# Keyboard_SYS.net
KiCad netlist of a schematic drawn in Altium Designer
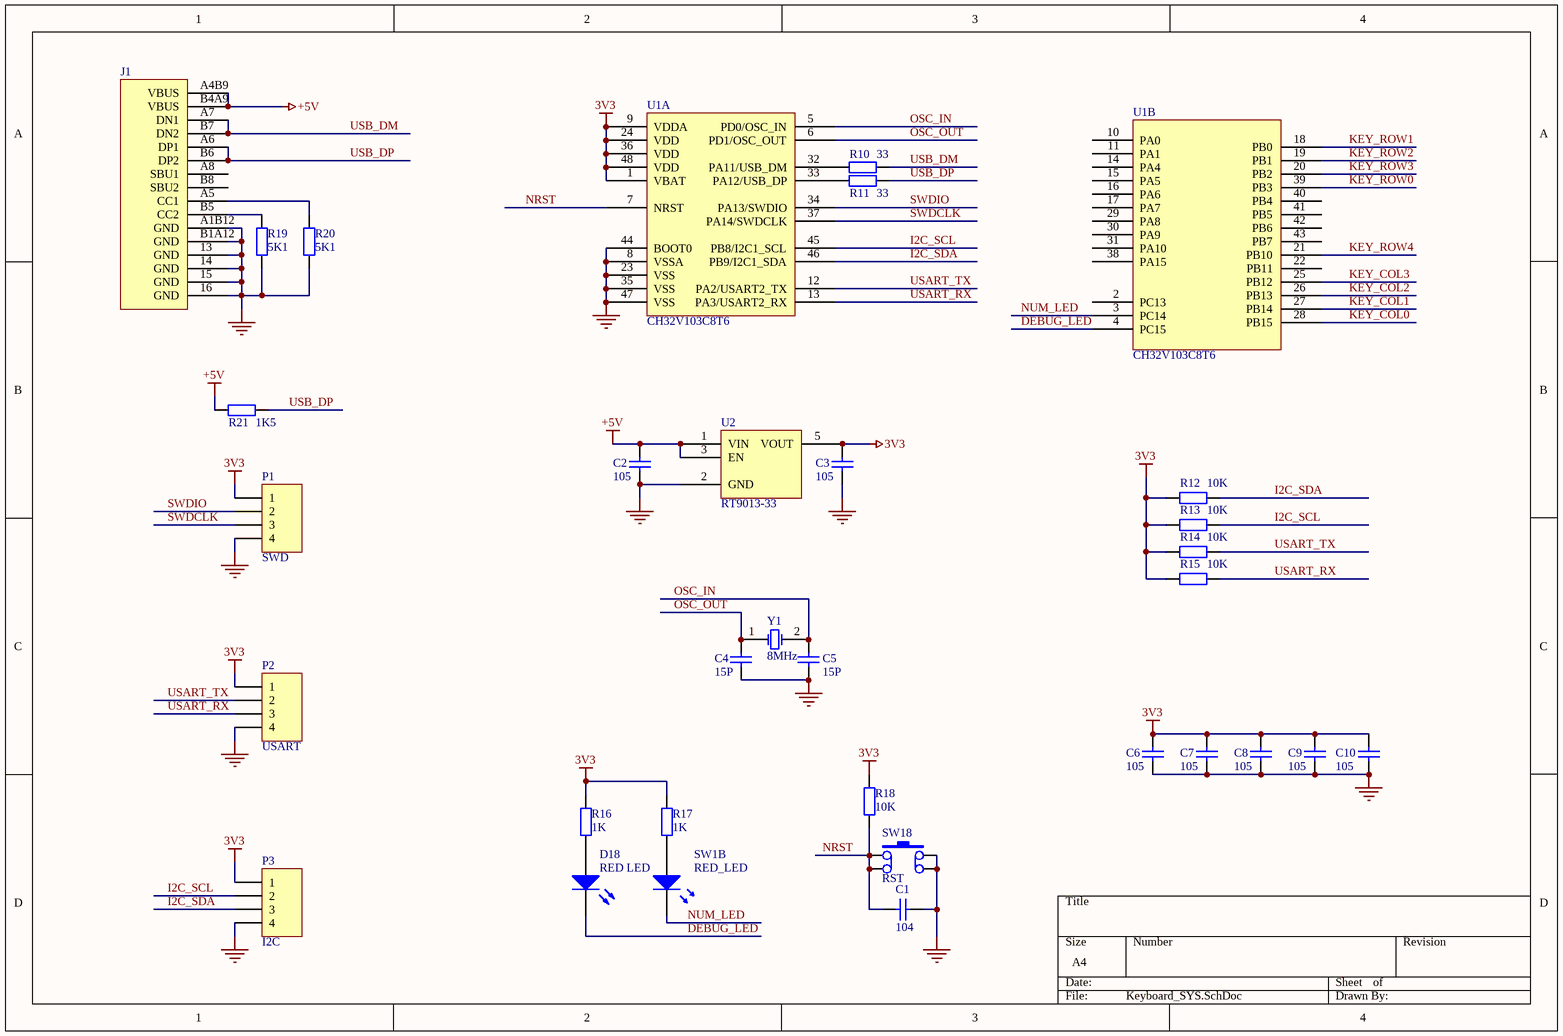
[diagram p0: Keyboard_SYS.SchDoc]

(export (version "E")
  (design (tool "Eeschema 10.0.6"))
  (components
    (comp (ref "C1")
      (value "104")
      (footprint "Devices:C0603")
      (description "Capacitor (Semiconductor SIM Model)")
      (fields (field (name "PUBLISHER") "Altium Limited"))
      (libsource (lib "Miscellaneous Devices") (part "Cap Semi"))
    )
    (comp (ref "C2")
      (value "105")
      (footprint "Devices:C0603")
      (description "Capacitor (Semiconductor SIM Model)")
      (fields (field (name "PUBLISHER") "Altium Limited"))
      (libsource (lib "Miscellaneous Devices") (part "Cap Semi"))
    )
    (comp (ref "C3")
      (value "105")
      (footprint "Devices:C0603")
      (description "Capacitor (Semiconductor SIM Model)")
      (fields (field (name "PUBLISHER") "Altium Limited"))
      (libsource (lib "Miscellaneous Devices") (part "Cap Semi"))
    )
    (comp (ref "C4")
      (value "15P")
      (footprint "Devices:C0603")
      (description "Capacitor (Semiconductor SIM Model)")
      (fields (field (name "PUBLISHER") "Altium Limited"))
      (libsource (lib "Miscellaneous Devices") (part "Cap Semi"))
    )
    (comp (ref "C5")
      (value "15P")
      (footprint "Devices:C0603")
      (description "Capacitor (Semiconductor SIM Model)")
      (fields (field (name "PUBLISHER") "Altium Limited"))
      (libsource (lib "Miscellaneous Devices") (part "Cap Semi"))
    )
    (comp (ref "C6")
      (value "105")
      (footprint "Devices:C0603")
      (description "Capacitor (Semiconductor SIM Model)")
      (fields (field (name "PUBLISHER") "Altium Limited"))
      (libsource (lib "Miscellaneous Devices") (part "Cap Semi"))
    )
    (comp (ref "C7")
      (value "105")
      (footprint "Devices:C0603")
      (description "Capacitor (Semiconductor SIM Model)")
      (fields (field (name "PUBLISHER") "Altium Limited"))
      (libsource (lib "Miscellaneous Devices") (part "Cap Semi"))
    )
    (comp (ref "C8")
      (value "105")
      (footprint "Devices:C0603")
      (description "Capacitor (Semiconductor SIM Model)")
      (fields (field (name "PUBLISHER") "Altium Limited"))
      (libsource (lib "Miscellaneous Devices") (part "Cap Semi"))
    )
    (comp (ref "C9")
      (value "105")
      (footprint "Devices:C0603")
      (description "Capacitor (Semiconductor SIM Model)")
      (fields (field (name "PUBLISHER") "Altium Limited"))
      (libsource (lib "Miscellaneous Devices") (part "Cap Semi"))
    )
    (comp (ref "C10")
      (value "105")
      (footprint "Devices:C0603")
      (description "Capacitor (Semiconductor SIM Model)")
      (fields (field (name "PUBLISHER") "Altium Limited"))
      (libsource (lib "Miscellaneous Devices") (part "Cap Semi"))
    )
    (comp (ref "D18")
      (value "RED LED")
      (footprint "Devices:LED0603-RED")
      (description "Typical RED, GREEN, YELLOW, AMBER GaAs LED")
      (fields (field (name "PUBLISHER") "Altium Limited"))
      (libsource (lib "Miscellaneous Devices") (part "LED2"))
    )
    (comp (ref "J1")
      (value "TYPEC-304S-ACP16")
      (footprint "Devices:USB-C-SMD_TYPEC-304-BCP16")
      (libsource (lib "Devices") (part "TYPEC-304S-ACP16"))
    )
    (comp (ref "P1")
      (value "SWD")
      (footprint "Devices:SIP4")
      (description "Header, 4-Pin")
      (fields (field (name "PUBLISHER") "Altium Limited"))
      (libsource (lib "Miscellaneous Connectors") (part "Header 4"))
    )
    (comp (ref "P2")
      (value "USART")
      (footprint "Devices:SIP4")
      (description "Header, 4-Pin")
      (fields (field (name "PUBLISHER") "Altium Limited"))
      (libsource (lib "Miscellaneous Connectors") (part "Header 4"))
    )
    (comp (ref "P3")
      (value "I2C")
      (footprint "Devices:SIP4")
      (description "Header, 4-Pin")
      (fields (field (name "PUBLISHER") "Altium Limited"))
      (libsource (lib "Miscellaneous Connectors") (part "Header 4"))
    )
    (comp (ref "R10")
      (value "33")
      (footprint "Devices:R0603")
      (description "Resistor")
      (fields (field (name "PUBLISHER") "Altium Limited"))
      (libsource (lib "Miscellaneous Devices") (part "Res2"))
    )
    (comp (ref "R11")
      (value "33")
      (footprint "Devices:R0603")
      (description "Resistor")
      (fields (field (name "PUBLISHER") "Altium Limited"))
      (libsource (lib "Miscellaneous Devices") (part "Res2"))
    )
    (comp (ref "R12")
      (value "10K")
      (footprint "Devices:R0603")
      (description "Resistor")
      (fields (field (name "PUBLISHER") "Altium Limited"))
      (libsource (lib "") (part "Res2_3"))
    )
    (comp (ref "R13")
      (value "10K")
      (footprint "Devices:R0603")
      (description "Resistor")
      (fields (field (name "PUBLISHER") "Altium Limited"))
      (libsource (lib "") (part "Res2_3"))
    )
    (comp (ref "R14")
      (value "10K")
      (footprint "Devices:R0603")
      (description "Resistor")
      (fields (field (name "PUBLISHER") "Altium Limited"))
      (libsource (lib "") (part "Res2_3"))
    )
    (comp (ref "R15")
      (value "10K")
      (footprint "Devices:R0603")
      (description "Resistor")
      (fields (field (name "PUBLISHER") "Altium Limited"))
      (libsource (lib "") (part "Res2_3"))
    )
    (comp (ref "R16")
      (value "1K")
      (footprint "Devices:R0603")
      (description "Resistor")
      (fields (field (name "PUBLISHER") "Altium Limited"))
      (libsource (lib "") (part "Res2_2"))
    )
    (comp (ref "R17")
      (value "1K")
      (footprint "Devices:R0603")
      (description "Resistor")
      (fields (field (name "PUBLISHER") "Altium Limited"))
      (libsource (lib "") (part "Res2_2"))
    )
    (comp (ref "R18")
      (value "10K")
      (footprint "Devices:R0603")
      (description "Resistor")
      (fields (field (name "PUBLISHER") "Altium Limited"))
      (libsource (lib "") (part "Res2_1"))
    )
    (comp (ref "R19")
      (value "5K1")
      (footprint "Devices:R0603")
      (description "Resistor")
      (fields (field (name "PUBLISHER") "Altium Limited"))
      (libsource (lib "") (part "Res2_1"))
    )
    (comp (ref "R20")
      (value "5K1")
      (footprint "Devices:R0603")
      (description "Resistor")
      (fields (field (name "PUBLISHER") "Altium Limited"))
      (libsource (lib "") (part "Res2_1"))
    )
    (comp (ref "R21")
      (value "1K5")
      (footprint "Devices:R0603")
      (description "Resistor")
      (fields (field (name "PUBLISHER") "Altium Limited"))
      (libsource (lib "Miscellaneous Devices") (part "Res2"))
    )
    (comp (ref "SW1")
      (value "RED_LED")
      (footprint "Devices:MX_SW-4-1206LED")
      (libsource (lib "Devices") (part "MX_SW-4-1206LED"))
    )
    (comp (ref "SW18")
      (value "RST")
      (footprint "Devices:Push Buttom SMD")
      (libsource (lib "Devices") (part "Push Buttom"))
    )
    (comp (ref "U1")
      (value "CH32V103C8T6")
      (footprint "Devices:PQFP48")
      (description "STM32F103C8Tx series arm mcu")
      (libsource (lib "Devices") (part "STM32F103C8Tx"))
    )
    (comp (ref "U2")
      (value "RT9013-33")
      (footprint "Devices:SOT-23-5")
      (description "RT9013 3.3V  LDO Regulator")
      (libsource (lib "Devices") (part "RT9013-33"))
    )
    (comp (ref "Y1")
      (value "8MHz")
      (footprint "Devices:CY5032")
      (description "Crystal Oscillator")
      (fields (field (name "PUBLISHER") "Altium Limited"))
      (libsource (lib "Miscellaneous Devices") (part "XTAL"))
    )
  )
  (nets
    (net (code "1") (name "+5V") (class "Default")
      (node (ref "C2") (pin "2") (pinfunction "2_2") (pintype "passive"))
      (node (ref "J1") (pin "A4B9") (pinfunction "VBUS_A4B9") (pintype "passive"))
      (node (ref "J1") (pin "B4A9") (pinfunction "VBUS_B4A9") (pintype "passive"))
      (node (ref "R21") (pin "1") (pinfunction "1_1") (pintype "passive"))
      (node (ref "U2") (pin "1") (pinfunction "VIN_1") (pintype "passive"))
      (node (ref "U2") (pin "3") (pinfunction "EN_3") (pintype "passive"))
    )
    (net (code "2") (name "/DEBUG_LED") (class "Default")
      (node (ref "D18") (pin "2") (pinfunction "K_2") (pintype "passive"))
      (node (ref "U1") (pin "4") (pinfunction "PC15_4") (pintype "passive"))
    )
    (net (code "3") (name "/I2C_SCL") (class "Default")
      (node (ref "P3") (pin "2") (pinfunction "2_2") (pintype "passive"))
      (node (ref "R13") (pin "1") (pinfunction "1_1") (pintype "passive"))
      (node (ref "U1") (pin "45") (pinfunction "PB8/I2C1_SCL_45") (pintype "passive"))
    )
    (net (code "4") (name "/I2C_SDA") (class "Default")
      (node (ref "P3") (pin "3") (pinfunction "3_3") (pintype "passive"))
      (node (ref "R12") (pin "1") (pinfunction "1_1") (pintype "passive"))
      (node (ref "U1") (pin "46") (pinfunction "PB9/I2C1_SDA_46") (pintype "passive"))
    )
    (net (code "5") (name "/KEY_COL0") (class "Default")
      (node (ref "U1") (pin "28") (pinfunction "PB15_28") (pintype "passive"))
    )
    (net (code "6") (name "/KEY_COL1") (class "Default")
      (node (ref "U1") (pin "27") (pinfunction "PB14_27") (pintype "passive"))
    )
    (net (code "7") (name "/KEY_COL2") (class "Default")
      (node (ref "U1") (pin "26") (pinfunction "PB13_26") (pintype "passive"))
    )
    (net (code "8") (name "/KEY_COL3") (class "Default")
      (node (ref "U1") (pin "25") (pinfunction "PB12_25") (pintype "passive"))
    )
    (net (code "9") (name "/KEY_ROW0") (class "Default")
      (node (ref "U1") (pin "39") (pinfunction "PB3_39") (pintype "passive"))
    )
    (net (code "10") (name "/KEY_ROW1") (class "Default")
      (node (ref "U1") (pin "18") (pinfunction "PB0_18") (pintype "passive"))
    )
    (net (code "11") (name "/KEY_ROW2") (class "Default")
      (node (ref "U1") (pin "19") (pinfunction "PB1_19") (pintype "passive"))
    )
    (net (code "12") (name "/KEY_ROW3") (class "Default")
      (node (ref "U1") (pin "20") (pinfunction "PB2_20") (pintype "passive"))
    )
    (net (code "13") (name "/KEY_ROW4") (class "Default")
      (node (ref "U1") (pin "21") (pinfunction "PB10_21") (pintype "passive"))
    )
    (net (code "14") (name "/NRST") (class "Default")
      (node (ref "C1") (pin "2") (pinfunction "2_2") (pintype "passive"))
      (node (ref "R18") (pin "2") (pinfunction "2_2") (pintype "passive"))
      (node (ref "SW18") (pin "1") (pinfunction "1_1") (pintype "passive"))
      (node (ref "SW18") (pin "2") (pinfunction "2_2") (pintype "passive"))
      (node (ref "U1") (pin "7") (pinfunction "NRST_7") (pintype "passive"))
    )
    (net (code "15") (name "/NUM_LED") (class "Default")
      (node (ref "SW1") (pin "4") (pinfunction "4_4") (pintype "passive"))
      (node (ref "U1") (pin "3") (pinfunction "PC14_3") (pintype "passive"))
    )
    (net (code "16") (name "/OSC_IN") (class "Default")
      (node (ref "C5") (pin "2") (pinfunction "2_2") (pintype "passive"))
      (node (ref "U1") (pin "5") (pinfunction "PD0/OSC_IN_5") (pintype "passive"))
      (node (ref "Y1") (pin "2") (pinfunction "OSC2_2") (pintype "passive"))
    )
    (net (code "17") (name "/OSC_OUT") (class "Default")
      (node (ref "C4") (pin "2") (pinfunction "2_2") (pintype "passive"))
      (node (ref "U1") (pin "6") (pinfunction "PD1/OSC_OUT_6") (pintype "passive"))
      (node (ref "Y1") (pin "1") (pinfunction "OSC1_1") (pintype "passive"))
    )
    (net (code "18") (name "/SWDCLK") (class "Default")
      (node (ref "P1") (pin "3") (pinfunction "3_3") (pintype "passive"))
      (node (ref "U1") (pin "37") (pinfunction "PA14/SWDCLK_37") (pintype "passive"))
    )
    (net (code "19") (name "/SWDIO") (class "Default")
      (node (ref "P1") (pin "2") (pinfunction "2_2") (pintype "passive"))
      (node (ref "U1") (pin "34") (pinfunction "PA13/SWDIO_34") (pintype "passive"))
    )
    (net (code "20") (name "/USART_RX") (class "Default")
      (node (ref "P2") (pin "3") (pinfunction "3_3") (pintype "passive"))
      (node (ref "R15") (pin "1") (pinfunction "1_1") (pintype "passive"))
      (node (ref "U1") (pin "13") (pinfunction "PA3/USART2_RX_13") (pintype "passive"))
    )
    (net (code "21") (name "/USART_TX") (class "Default")
      (node (ref "P2") (pin "2") (pinfunction "2_2") (pintype "passive"))
      (node (ref "R14") (pin "1") (pinfunction "1_1") (pintype "passive"))
      (node (ref "U1") (pin "12") (pinfunction "PA2/USART2_TX_12") (pintype "passive"))
    )
    (net (code "22") (name "/USB_DM") (class "Default")
      (node (ref "J1") (pin "A7") (pinfunction "DN1_A7") (pintype "passive"))
      (node (ref "J1") (pin "B7") (pinfunction "DN2_B7") (pintype "passive"))
      (node (ref "R10") (pin "2") (pinfunction "2_2") (pintype "passive"))
    )
    (net (code "23") (name "/USB_DP") (class "Default")
      (node (ref "J1") (pin "A6") (pinfunction "DP1_A6") (pintype "passive"))
      (node (ref "J1") (pin "B6") (pinfunction "DP2_B6") (pintype "passive"))
      (node (ref "R11") (pin "2") (pinfunction "2_2") (pintype "passive"))
      (node (ref "R21") (pin "2") (pinfunction "2_2") (pintype "passive"))
    )
    (net (code "24") (name "3V3") (class "Default")
      (node (ref "C10") (pin "2") (pinfunction "2_2") (pintype "passive"))
      (node (ref "C3") (pin "2") (pinfunction "2_2") (pintype "passive"))
      (node (ref "C6") (pin "2") (pinfunction "2_2") (pintype "passive"))
      (node (ref "C7") (pin "2") (pinfunction "2_2") (pintype "passive"))
      (node (ref "C8") (pin "2") (pinfunction "2_2") (pintype "passive"))
      (node (ref "C9") (pin "2") (pinfunction "2_2") (pintype "passive"))
      (node (ref "P1") (pin "1") (pinfunction "1_1") (pintype "passive"))
      (node (ref "P2") (pin "1") (pinfunction "1_1") (pintype "passive"))
      (node (ref "P3") (pin "1") (pinfunction "1_1") (pintype "passive"))
      (node (ref "R12") (pin "2") (pinfunction "2_2") (pintype "passive"))
      (node (ref "R13") (pin "2") (pinfunction "2_2") (pintype "passive"))
      (node (ref "R14") (pin "2") (pinfunction "2_2") (pintype "passive"))
      (node (ref "R15") (pin "2") (pinfunction "2_2") (pintype "passive"))
      (node (ref "R16") (pin "2") (pinfunction "2_2") (pintype "passive"))
      (node (ref "R17") (pin "2") (pinfunction "2_2") (pintype "passive"))
      (node (ref "R18") (pin "1") (pinfunction "1_1") (pintype "passive"))
      (node (ref "U1") (pin "1") (pinfunction "VBAT_1") (pintype "passive"))
      (node (ref "U1") (pin "24") (pinfunction "VDD_24") (pintype "passive"))
      (node (ref "U1") (pin "36") (pinfunction "VDD_36") (pintype "passive"))
      (node (ref "U1") (pin "48") (pinfunction "VDD_48") (pintype "passive"))
      (node (ref "U1") (pin "9") (pinfunction "VDDA_9") (pintype "passive"))
      (node (ref "U2") (pin "5") (pinfunction "VOUT_5") (pintype "passive"))
    )
    (net (code "25") (name "GND") (class "Default")
      (node (ref "C1") (pin "1") (pinfunction "1_1") (pintype "passive"))
      (node (ref "C10") (pin "1") (pinfunction "1_1") (pintype "passive"))
      (node (ref "C2") (pin "1") (pinfunction "1_1") (pintype "passive"))
      (node (ref "C3") (pin "1") (pinfunction "1_1") (pintype "passive"))
      (node (ref "C4") (pin "1") (pinfunction "1_1") (pintype "passive"))
      (node (ref "C5") (pin "1") (pinfunction "1_1") (pintype "passive"))
      (node (ref "C6") (pin "1") (pinfunction "1_1") (pintype "passive"))
      (node (ref "C7") (pin "1") (pinfunction "1_1") (pintype "passive"))
      (node (ref "C8") (pin "1") (pinfunction "1_1") (pintype "passive"))
      (node (ref "C9") (pin "1") (pinfunction "1_1") (pintype "passive"))
      (node (ref "J1") (pin "13") (pinfunction "GND_13") (pintype "passive"))
      (node (ref "J1") (pin "14") (pinfunction "GND_14") (pintype "passive"))
      (node (ref "J1") (pin "15") (pinfunction "GND_15") (pintype "passive"))
      (node (ref "J1") (pin "16") (pinfunction "GND_16") (pintype "passive"))
      (node (ref "J1") (pin "A1B12") (pinfunction "GND_A1B12") (pintype "passive"))
      (node (ref "J1") (pin "B1A12") (pinfunction "GND_B1A12") (pintype "passive"))
      (node (ref "P1") (pin "4") (pinfunction "4_4") (pintype "passive"))
      (node (ref "P2") (pin "4") (pinfunction "4_4") (pintype "passive"))
      (node (ref "P3") (pin "4") (pinfunction "4_4") (pintype "passive"))
      (node (ref "R19") (pin "2") (pinfunction "2_2") (pintype "passive"))
      (node (ref "R20") (pin "2") (pinfunction "2_2") (pintype "passive"))
      (node (ref "SW18") (pin "3") (pinfunction "3_3") (pintype "passive"))
      (node (ref "SW18") (pin "4") (pinfunction "4_4") (pintype "passive"))
      (node (ref "U1") (pin "23") (pinfunction "VSS_23") (pintype "passive"))
      (node (ref "U1") (pin "35") (pinfunction "VSS_35") (pintype "passive"))
      (node (ref "U1") (pin "44") (pinfunction "BOOT0_44") (pintype "passive"))
      (node (ref "U1") (pin "47") (pinfunction "VSS_47") (pintype "passive"))
      (node (ref "U1") (pin "8") (pinfunction "VSSA_8") (pintype "passive"))
      (node (ref "U2") (pin "2") (pinfunction "GND_2") (pintype "passive"))
    )
    (net (code "26") (name "Net-(D18-A)") (class "Default")
      (node (ref "D18") (pin "1") (pinfunction "A_1") (pintype "passive"))
      (node (ref "R16") (pin "1") (pinfunction "1_1") (pintype "passive"))
    )
    (net (code "27") (name "Net-(J1-CC1)") (class "Default")
      (node (ref "J1") (pin "A5") (pinfunction "CC1_A5") (pintype "passive"))
      (node (ref "R20") (pin "1") (pinfunction "1_1") (pintype "passive"))
    )
    (net (code "28") (name "Net-(J1-CC2)") (class "Default")
      (node (ref "J1") (pin "B5") (pinfunction "CC2_B5") (pintype "passive"))
      (node (ref "R19") (pin "1") (pinfunction "1_1") (pintype "passive"))
    )
    (net (code "29") (name "Net-(R17-Pad1)") (class "Default")
      (node (ref "R17") (pin "1") (pinfunction "1_1") (pintype "passive"))
      (node (ref "SW1") (pin "3") (pinfunction "3_3") (pintype "passive"))
    )
    (net (code "30") (name "Net-(U1A-PA11{slash}USB_DM)") (class "Default")
      (node (ref "R10") (pin "1") (pinfunction "1_1") (pintype "passive"))
      (node (ref "U1") (pin "32") (pinfunction "PA11/USB_DM_32") (pintype "passive"))
    )
    (net (code "31") (name "Net-(U1A-PA12{slash}USB_DP)") (class "Default")
      (node (ref "R11") (pin "1") (pinfunction "1_1") (pintype "passive"))
      (node (ref "U1") (pin "33") (pinfunction "PA12/USB_DP_33") (pintype "passive"))
    )
    (net (code "32") (name "unconnected-(J1-SBU1-PadA8)") (class "Default")
      (node (ref "J1") (pin "A8") (pinfunction "SBU1_A8") (pintype "passive"))
    )
    (net (code "33") (name "unconnected-(J1-SBU2-PadB8)") (class "Default")
      (node (ref "J1") (pin "B8") (pinfunction "SBU2_B8") (pintype "passive"))
    )
    (net (code "34") (name "unconnected-(U1B-PA0-Pad10)") (class "Default")
      (node (ref "U1") (pin "10") (pinfunction "PA0_10") (pintype "passive"))
    )
    (net (code "35") (name "unconnected-(U1B-PA1-Pad11)") (class "Default")
      (node (ref "U1") (pin "11") (pinfunction "PA1_11") (pintype "passive"))
    )
    (net (code "36") (name "unconnected-(U1B-PA4-Pad14)") (class "Default")
      (node (ref "U1") (pin "14") (pinfunction "PA4_14") (pintype "passive"))
    )
    (net (code "37") (name "unconnected-(U1B-PA5-Pad15)") (class "Default")
      (node (ref "U1") (pin "15") (pinfunction "PA5_15") (pintype "passive"))
    )
    (net (code "38") (name "unconnected-(U1B-PA6-Pad16)") (class "Default")
      (node (ref "U1") (pin "16") (pinfunction "PA6_16") (pintype "passive"))
    )
    (net (code "39") (name "unconnected-(U1B-PA7-Pad17)") (class "Default")
      (node (ref "U1") (pin "17") (pinfunction "PA7_17") (pintype "passive"))
    )
    (net (code "40") (name "unconnected-(U1B-PA8-Pad29)") (class "Default")
      (node (ref "U1") (pin "29") (pinfunction "PA8_29") (pintype "passive"))
    )
    (net (code "41") (name "unconnected-(U1B-PA9-Pad30)") (class "Default")
      (node (ref "U1") (pin "30") (pinfunction "PA9_30") (pintype "passive"))
    )
    (net (code "42") (name "unconnected-(U1B-PA10-Pad31)") (class "Default")
      (node (ref "U1") (pin "31") (pinfunction "PA10_31") (pintype "passive"))
    )
    (net (code "43") (name "unconnected-(U1B-PA15-Pad38)") (class "Default")
      (node (ref "U1") (pin "38") (pinfunction "PA15_38") (pintype "passive"))
    )
    (net (code "44") (name "unconnected-(U1B-PB4-Pad40)") (class "Default")
      (node (ref "U1") (pin "40") (pinfunction "PB4_40") (pintype "passive"))
    )
    (net (code "45") (name "unconnected-(U1B-PB5-Pad41)") (class "Default")
      (node (ref "U1") (pin "41") (pinfunction "PB5_41") (pintype "passive"))
    )
    (net (code "46") (name "unconnected-(U1B-PB6-Pad42)") (class "Default")
      (node (ref "U1") (pin "42") (pinfunction "PB6_42") (pintype "passive"))
    )
    (net (code "47") (name "unconnected-(U1B-PB7-Pad43)") (class "Default")
      (node (ref "U1") (pin "43") (pinfunction "PB7_43") (pintype "passive"))
    )
    (net (code "48") (name "unconnected-(U1B-PB11-Pad22)") (class "Default")
      (node (ref "U1") (pin "22") (pinfunction "PB11_22") (pintype "passive"))
    )
    (net (code "49") (name "unconnected-(U1B-PC13-Pad2)") (class "Default")
      (node (ref "U1") (pin "2") (pinfunction "PC13_2") (pintype "passive"))
    )
    (net (code "50") (name "unconnected-(U2-NC-Pad4)") (class "Default")
      (node (ref "U2") (pin "4") (pinfunction "NC_4") (pintype "passive"))
    )
  )
)
